# PCI_short_card_universal_-_32_BIT.net
KiCad netlist of a schematic drawn in Altium Designer
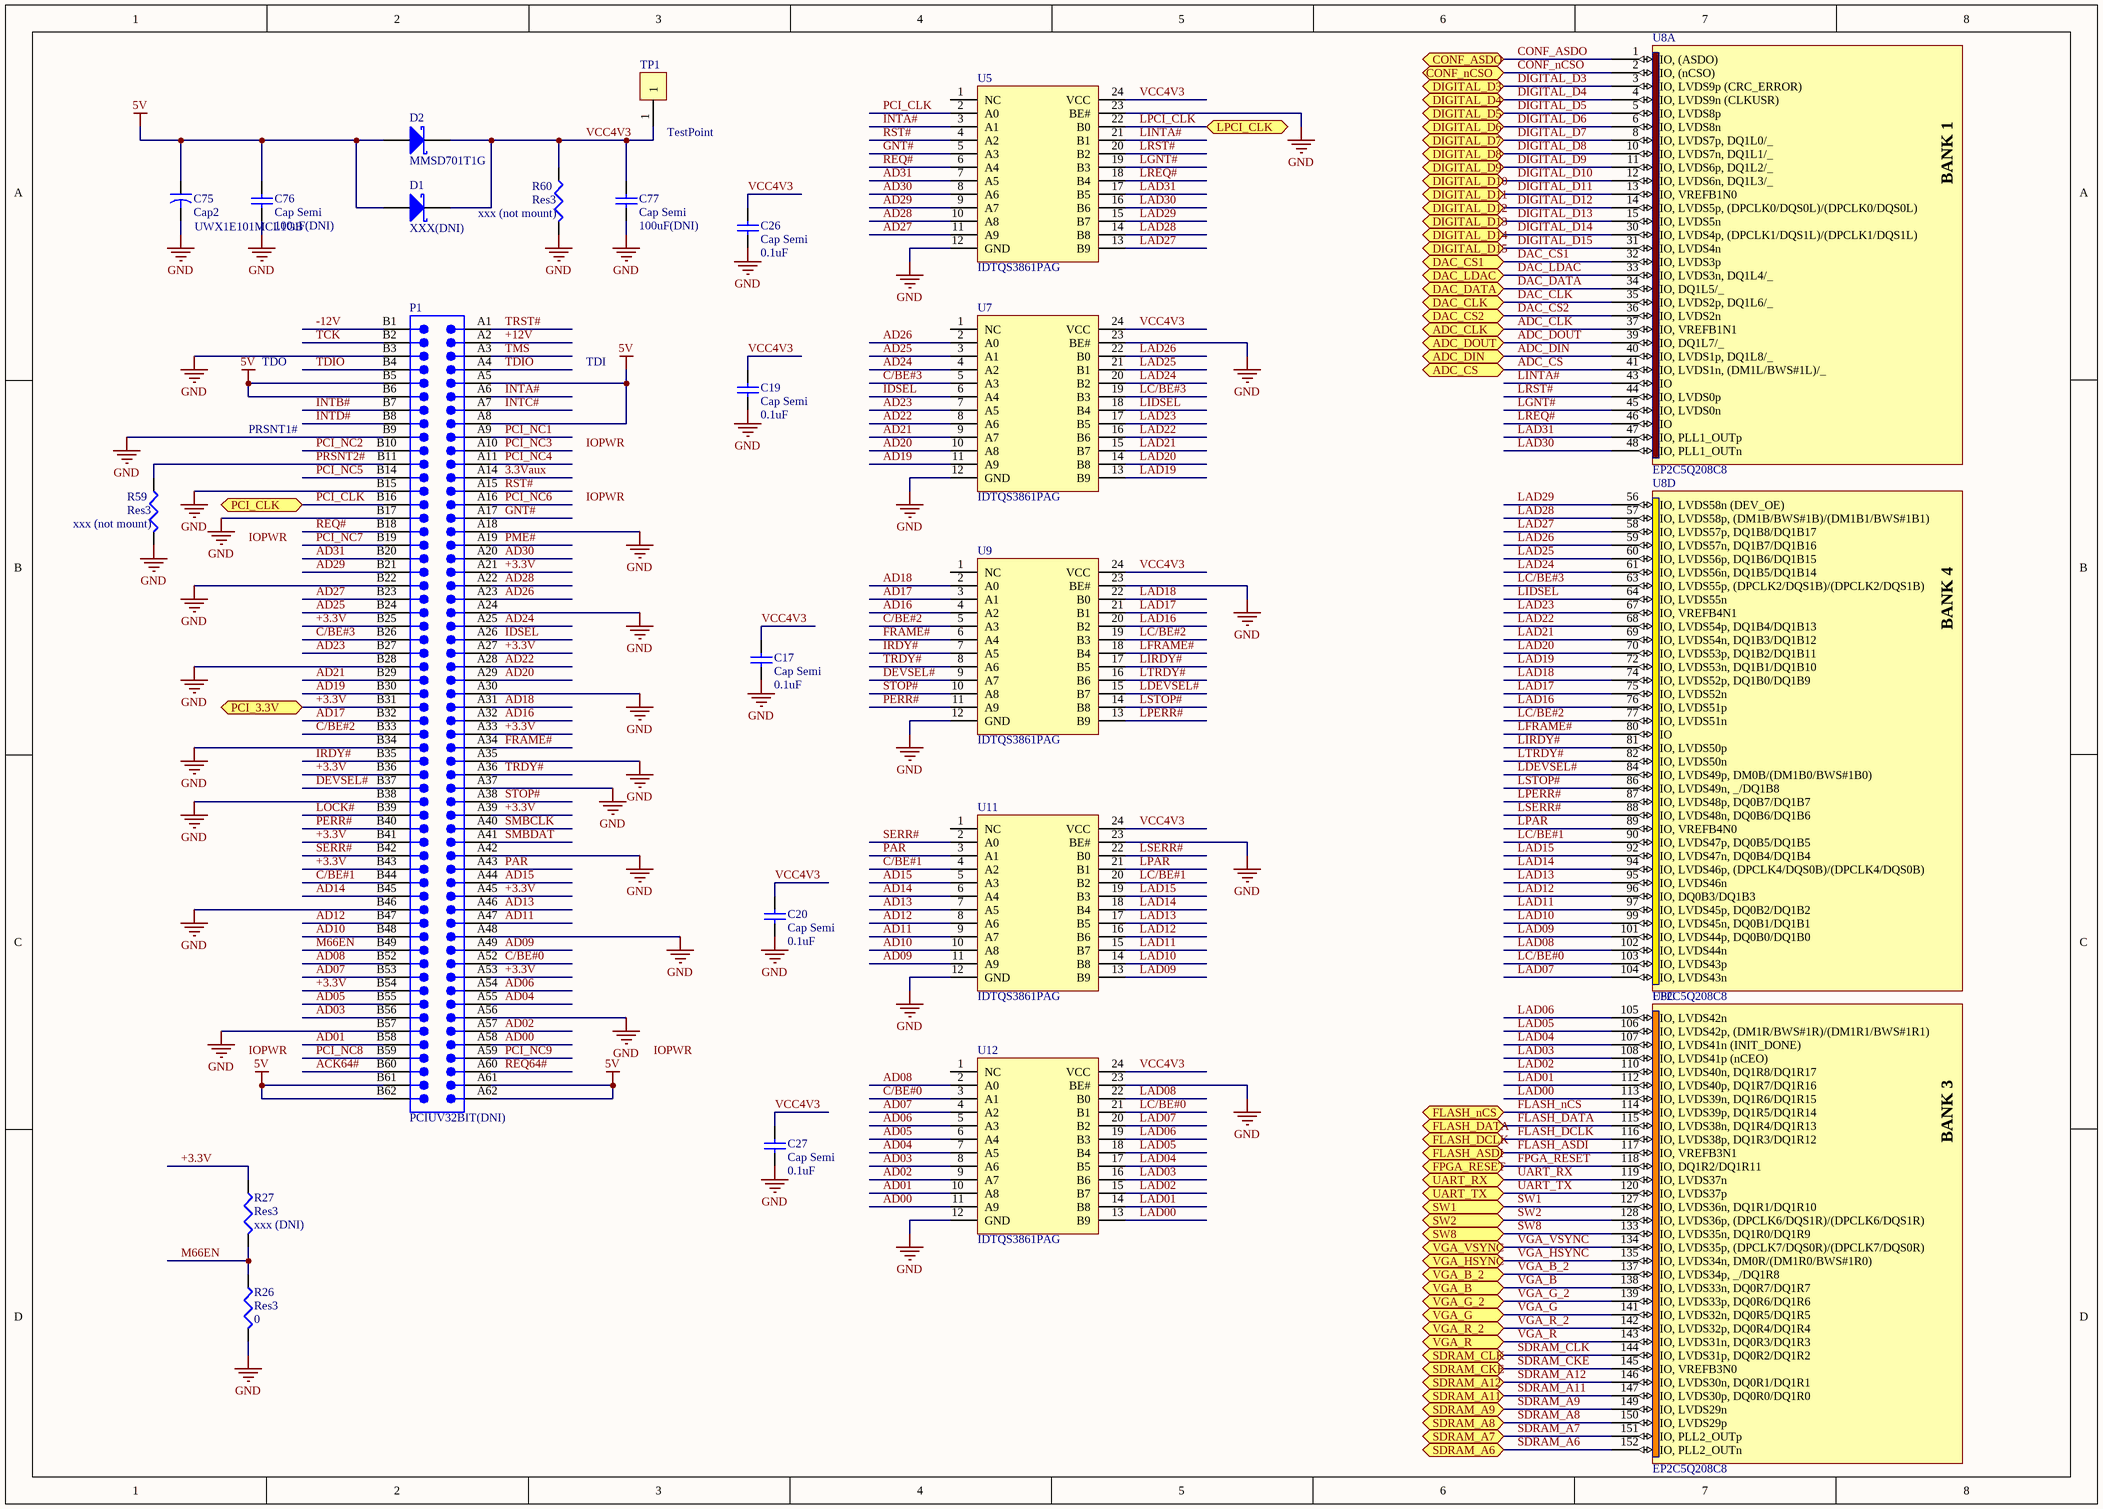
[diagram p0: PCI short card universal - 32 BIT.schdoc]

(export (version "E")
  (design (tool "Eeschema 10.0.6"))
  (components
    (comp (ref "C17")
      (value "Cap Semi")
      (footprint "RESC1608N")
      (description "Capacitor (Semiconductor SIM Model)")
      (fields (field (name "ALTIUM_VALUE") "0.1uF") (field (name "PUBLISHER") "Altium Limited"))
      (libsource (lib "Miscellaneous Devices") (part "Cap Semi"))
    )
    (comp (ref "C19")
      (value "Cap Semi")
      (footprint "RESC1608N")
      (description "Capacitor (Semiconductor SIM Model)")
      (fields (field (name "ALTIUM_VALUE") "0.1uF") (field (name "PUBLISHER") "Altium Limited"))
      (libsource (lib "Miscellaneous Devices") (part "Cap Semi"))
    )
    (comp (ref "C20")
      (value "Cap Semi")
      (footprint "RESC1608N")
      (description "Capacitor (Semiconductor SIM Model)")
      (fields (field (name "ALTIUM_VALUE") "0.1uF") (field (name "PUBLISHER") "Altium Limited"))
      (libsource (lib "Miscellaneous Devices") (part "Cap Semi"))
    )
    (comp (ref "C26")
      (value "Cap Semi")
      (footprint "RESC1608N")
      (description "Capacitor (Semiconductor SIM Model)")
      (fields (field (name "ALTIUM_VALUE") "0.1uF") (field (name "PUBLISHER") "Altium Limited"))
      (libsource (lib "Miscellaneous Devices") (part "Cap Semi"))
    )
    (comp (ref "C27")
      (value "Cap Semi")
      (footprint "RESC1608N")
      (description "Capacitor (Semiconductor SIM Model)")
      (fields (field (name "ALTIUM_VALUE") "0.1uF") (field (name "PUBLISHER") "Altium Limited"))
      (libsource (lib "Miscellaneous Devices") (part "Cap Semi"))
    )
    (comp (ref "C75")
      (value "Cap2")
      (footprint "ECEL_D8")
      (description "NICHICON")
      (fields (field (name "ALTIUM_VALUE") "UWX1E101MCL1GB") (field (name "PUBLISHER") "Altium Limited"))
      (libsource (lib "Miscellaneous Devices") (part "Cap2"))
    )
    (comp (ref "C76")
      (value "Cap Semi")
      (footprint "CD3225-1210")
      (fields (field (name "ALTIUM_VALUE") "100uF(DNI)") (field (name "PUBLISHER") "Altium Limited"))
      (libsource (lib "Miscellaneous Devices") (part "Cap Semi"))
    )
    (comp (ref "C77")
      (value "Cap Semi")
      (footprint "CD3225-1210")
      (fields (field (name "ALTIUM_VALUE") "100uF(DNI)") (field (name "PUBLISHER") "Altium Limited"))
      (libsource (lib "Miscellaneous Devices") (part "Cap Semi"))
    )
    (comp (ref "D1")
      (value "XXX(DNI)")
      (footprint "LED3.2X1.6X1.1")
      (description "Schottky Diode")
      (fields (field (name "PUBLISHER") "Altium Limited"))
      (libsource (lib "Miscellaneous Devices") (part "D Schottky"))
    )
    (comp (ref "D2")
      (value "MMSD701T1G")
      (footprint "SOD-123")
      (description "ON SEMI")
      (fields (field (name "PUBLISHER") "Altium Limited"))
      (libsource (lib "Miscellaneous Devices") (part "D Schottky"))
    )
    (comp (ref "P1")
      (value "PCIUV32BIT(DNI)")
      (footprint "PCIUV32BIT")
      (description "Card, 116-Position")
      (libsource (lib "*") (part "PCIUV32BIT"))
    )
    (comp (ref "R26")
      (value "Res3")
      (footprint "RESC1608N")
      (description "Resistor")
      (fields (field (name "ALTIUM_VALUE") "0") (field (name "PUBLISHER") "Altium Limited"))
      (libsource (lib "Miscellaneous Devices") (part "Res3"))
    )
    (comp (ref "R27")
      (value "Res3")
      (footprint "RESC1608N")
      (description "Resistor")
      (fields (field (name "ALTIUM_VALUE") "xxx (DNI)") (field (name "PUBLISHER") "Altium Limited"))
      (libsource (lib "Miscellaneous Devices") (part "Res3"))
    )
    (comp (ref "R59")
      (value "Res3")
      (footprint "RESC1608N")
      (description "Resistor")
      (fields (field (name "ALTIUM_VALUE") "xxx (not mount)") (field (name "PUBLISHER") "Altium Limited"))
      (libsource (lib "Miscellaneous Devices") (part "Res3"))
    )
    (comp (ref "R60")
      (value "Res3")
      (footprint "RESC1608N")
      (description "Resistor")
      (fields (field (name "ALTIUM_VALUE") "xxx (not mount)") (field (name "PUBLISHER") "Altium Limited"))
      (libsource (lib "Miscellaneous Devices") (part "Res3"))
    )
    (comp (ref "TP1") (value "TestPoint") (footprint "HDR1X1") (libsource (lib "Schlib1") (part "TestPoint")))
    (comp (ref "U5")
      (value "IDTQS3861PAG")
      (footprint "TSSOP24(QS3681)")
      (description "IDT")
      (libsource (lib "Schlib1") (part "QS3861"))
    )
    (comp (ref "U7")
      (value "IDTQS3861PAG")
      (footprint "TSSOP24(QS3681)")
      (description "IDT")
      (libsource (lib "Schlib1") (part "QS3861"))
    )
    (comp (ref "U8")
      (value "EP2C5Q208C8")
      (footprint "PQFP208_N")
      (fields (field (name "PUBLISHER") "Altium Limited"))
      (libsource (lib "Altera Cyclone II") (part "EP2C5Q208C8"))
    )
    (comp (ref "U9")
      (value "IDTQS3861PAG")
      (footprint "TSSOP24(QS3681)")
      (description "IDT")
      (libsource (lib "Schlib1") (part "QS3861"))
    )
    (comp (ref "U11")
      (value "IDTQS3861PAG")
      (footprint "TSSOP24(QS3681)")
      (description "IDT")
      (libsource (lib "Schlib1") (part "QS3861"))
    )
    (comp (ref "U12")
      (value "IDTQS3861PAG")
      (footprint "TSSOP24(QS3681)")
      (description "IDT")
      (libsource (lib "Schlib1") (part "QS3861"))
    )
  )
  (nets
    (net (code "1") (name "/+3.3V") (class "Default")
      (node (ref "P1") (pin "A21") (pinfunction "A21_A21") (pintype "passive"))
      (node (ref "P1") (pin "A27") (pinfunction "A27_A27") (pintype "passive"))
      (node (ref "P1") (pin "A33") (pinfunction "A33_A33") (pintype "passive"))
      (node (ref "P1") (pin "A39") (pinfunction "A39_A39") (pintype "passive"))
      (node (ref "P1") (pin "A45") (pinfunction "A45_A45") (pintype "passive"))
      (node (ref "P1") (pin "A53") (pinfunction "A53_A53") (pintype "passive"))
      (node (ref "P1") (pin "B25") (pinfunction "B25_B25") (pintype "passive"))
      (node (ref "P1") (pin "B31") (pinfunction "B31_B31") (pintype "passive"))
      (node (ref "P1") (pin "B36") (pinfunction "B36_B36") (pintype "passive"))
      (node (ref "P1") (pin "B41") (pinfunction "B41_B41") (pintype "passive"))
      (node (ref "P1") (pin "B43") (pinfunction "B43_B43") (pintype "passive"))
      (node (ref "P1") (pin "B54") (pinfunction "B54_B54") (pintype "passive"))
      (node (ref "R27") (pin "1") (pinfunction "1_1") (pintype "passive"))
    )
    (net (code "2") (name "/+12V") (class "Default")
      (node (ref "P1") (pin "A2") (pinfunction "A2_A2") (pintype "passive"))
    )
    (net (code "3") (name "/-12V") (class "Default")
      (node (ref "P1") (pin "B1") (pinfunction "B1_B1") (pintype "passive"))
    )
    (net (code "4") (name "/3.3Vaux") (class "Default")
      (node (ref "P1") (pin "A14") (pinfunction "A14_A14") (pintype "passive"))
    )
    (net (code "5") (name "/ACK64#") (class "Default")
      (node (ref "P1") (pin "B60") (pinfunction "B60_B60") (pintype "passive"))
    )
    (net (code "6") (name "/AD00") (class "Default")
      (node (ref "P1") (pin "A58") (pinfunction "A58_A58") (pintype "passive"))
      (node (ref "U12") (pin "11") (pinfunction "A9_11") (pintype "passive"))
    )
    (net (code "7") (name "/AD01") (class "Default")
      (node (ref "P1") (pin "B58") (pinfunction "B58_B58") (pintype "passive"))
      (node (ref "U12") (pin "10") (pinfunction "A8_10") (pintype "passive"))
    )
    (net (code "8") (name "/AD02") (class "Default")
      (node (ref "P1") (pin "A57") (pinfunction "A57_A57") (pintype "passive"))
      (node (ref "U12") (pin "9") (pinfunction "A7_9") (pintype "passive"))
    )
    (net (code "9") (name "/AD03") (class "Default")
      (node (ref "P1") (pin "B56") (pinfunction "B56_B56") (pintype "passive"))
      (node (ref "U12") (pin "8") (pinfunction "A6_8") (pintype "passive"))
    )
    (net (code "10") (name "/AD04") (class "Default")
      (node (ref "P1") (pin "A55") (pinfunction "A55_A55") (pintype "passive"))
      (node (ref "U12") (pin "7") (pinfunction "A5_7") (pintype "passive"))
    )
    (net (code "11") (name "/AD05") (class "Default")
      (node (ref "P1") (pin "B55") (pinfunction "B55_B55") (pintype "passive"))
      (node (ref "U12") (pin "6") (pinfunction "A4_6") (pintype "passive"))
    )
    (net (code "12") (name "/AD06") (class "Default")
      (node (ref "P1") (pin "A54") (pinfunction "A54_A54") (pintype "passive"))
      (node (ref "U12") (pin "5") (pinfunction "A3_5") (pintype "passive"))
    )
    (net (code "13") (name "/AD07") (class "Default")
      (node (ref "P1") (pin "B53") (pinfunction "B53_B53") (pintype "passive"))
      (node (ref "U12") (pin "4") (pinfunction "A2_4") (pintype "passive"))
    )
    (net (code "14") (name "/AD08") (class "Default")
      (node (ref "P1") (pin "B52") (pinfunction "B52_B52") (pintype "passive"))
      (node (ref "U12") (pin "2") (pinfunction "A0_2") (pintype "passive"))
    )
    (net (code "15") (name "/AD09") (class "Default")
      (node (ref "P1") (pin "A49") (pinfunction "A49_A49") (pintype "passive"))
      (node (ref "U11") (pin "11") (pinfunction "A9_11") (pintype "passive"))
    )
    (net (code "16") (name "/AD10") (class "Default")
      (node (ref "P1") (pin "B48") (pinfunction "B48_B48") (pintype "passive"))
      (node (ref "U11") (pin "10") (pinfunction "A8_10") (pintype "passive"))
    )
    (net (code "17") (name "/AD11") (class "Default")
      (node (ref "P1") (pin "A47") (pinfunction "A47_A47") (pintype "passive"))
      (node (ref "U11") (pin "9") (pinfunction "A7_9") (pintype "passive"))
    )
    (net (code "18") (name "/AD12") (class "Default")
      (node (ref "P1") (pin "B47") (pinfunction "B47_B47") (pintype "passive"))
      (node (ref "U11") (pin "8") (pinfunction "A6_8") (pintype "passive"))
    )
    (net (code "19") (name "/AD13") (class "Default")
      (node (ref "P1") (pin "A46") (pinfunction "A46_A46") (pintype "passive"))
      (node (ref "U11") (pin "7") (pinfunction "A5_7") (pintype "passive"))
    )
    (net (code "20") (name "/AD14") (class "Default")
      (node (ref "P1") (pin "B45") (pinfunction "B45_B45") (pintype "passive"))
      (node (ref "U11") (pin "6") (pinfunction "A4_6") (pintype "passive"))
    )
    (net (code "21") (name "/AD15") (class "Default")
      (node (ref "P1") (pin "A44") (pinfunction "A44_A44") (pintype "passive"))
      (node (ref "U11") (pin "5") (pinfunction "A3_5") (pintype "passive"))
    )
    (net (code "22") (name "/AD16") (class "Default")
      (node (ref "P1") (pin "A32") (pinfunction "A32_A32") (pintype "passive"))
      (node (ref "U9") (pin "4") (pinfunction "A2_4") (pintype "passive"))
    )
    (net (code "23") (name "/AD17") (class "Default")
      (node (ref "P1") (pin "B32") (pinfunction "B32_B32") (pintype "passive"))
      (node (ref "U9") (pin "3") (pinfunction "A1_3") (pintype "passive"))
    )
    (net (code "24") (name "/AD18") (class "Default")
      (node (ref "P1") (pin "A31") (pinfunction "A31_A31") (pintype "passive"))
      (node (ref "U9") (pin "2") (pinfunction "A0_2") (pintype "passive"))
    )
    (net (code "25") (name "/AD19") (class "Default")
      (node (ref "P1") (pin "B30") (pinfunction "B30_B30") (pintype "passive"))
      (node (ref "U7") (pin "11") (pinfunction "A9_11") (pintype "passive"))
    )
    (net (code "26") (name "/AD20") (class "Default")
      (node (ref "P1") (pin "A29") (pinfunction "A29_A29") (pintype "passive"))
      (node (ref "U7") (pin "10") (pinfunction "A8_10") (pintype "passive"))
    )
    (net (code "27") (name "/AD21") (class "Default")
      (node (ref "P1") (pin "B29") (pinfunction "B29_B29") (pintype "passive"))
      (node (ref "U7") (pin "9") (pinfunction "A7_9") (pintype "passive"))
    )
    (net (code "28") (name "/AD22") (class "Default")
      (node (ref "P1") (pin "A28") (pinfunction "A28_A28") (pintype "passive"))
      (node (ref "U7") (pin "8") (pinfunction "A6_8") (pintype "passive"))
    )
    (net (code "29") (name "/AD23") (class "Default")
      (node (ref "P1") (pin "B27") (pinfunction "B27_B27") (pintype "passive"))
      (node (ref "U7") (pin "7") (pinfunction "A5_7") (pintype "passive"))
    )
    (net (code "30") (name "/AD24") (class "Default")
      (node (ref "P1") (pin "A25") (pinfunction "A25_A25") (pintype "passive"))
      (node (ref "U7") (pin "4") (pinfunction "A2_4") (pintype "passive"))
    )
    (net (code "31") (name "/AD25") (class "Default")
      (node (ref "P1") (pin "B24") (pinfunction "B24_B24") (pintype "passive"))
      (node (ref "U7") (pin "3") (pinfunction "A1_3") (pintype "passive"))
    )
    (net (code "32") (name "/AD26") (class "Default")
      (node (ref "P1") (pin "A23") (pinfunction "A23_A23") (pintype "passive"))
      (node (ref "U7") (pin "2") (pinfunction "A0_2") (pintype "passive"))
    )
    (net (code "33") (name "/AD27") (class "Default")
      (node (ref "P1") (pin "B23") (pinfunction "B23_B23") (pintype "passive"))
      (node (ref "U5") (pin "11") (pinfunction "A9_11") (pintype "passive"))
    )
    (net (code "34") (name "/AD28") (class "Default")
      (node (ref "P1") (pin "A22") (pinfunction "A22_A22") (pintype "passive"))
      (node (ref "U5") (pin "10") (pinfunction "A8_10") (pintype "passive"))
    )
    (net (code "35") (name "/AD29") (class "Default")
      (node (ref "P1") (pin "B21") (pinfunction "B21_B21") (pintype "passive"))
      (node (ref "U5") (pin "9") (pinfunction "A7_9") (pintype "passive"))
    )
    (net (code "36") (name "/AD30") (class "Default")
      (node (ref "P1") (pin "A20") (pinfunction "A20_A20") (pintype "passive"))
      (node (ref "U5") (pin "8") (pinfunction "A6_8") (pintype "passive"))
    )
    (net (code "37") (name "/AD31") (class "Default")
      (node (ref "P1") (pin "B20") (pinfunction "B20_B20") (pintype "passive"))
      (node (ref "U5") (pin "7") (pinfunction "A5_7") (pintype "passive"))
    )
    (net (code "38") (name "/ADC_CLK") (class "Default")
      (node (ref "U8") (pin "37") (pinfunction "IO,_VREFB1N1_37") (pintype "bidirectional"))
    )
    (net (code "39") (name "/ADC_CS") (class "Default")
      (node (ref "U8") (pin "41") (pinfunction "IO,_LVDS1n,_(DM1L/BWS#1L)/__41") (pintype "bidirectional"))
    )
    (net (code "40") (name "/ADC_DIN") (class "Default")
      (node (ref "U8") (pin "40") (pinfunction "IO,_LVDS1p,_DQ1L8/__40") (pintype "bidirectional"))
    )
    (net (code "41") (name "/ADC_DOUT") (class "Default")
      (node (ref "U8") (pin "39") (pinfunction "IO,_DQ1L7/__39") (pintype "bidirectional"))
    )
    (net (code "42") (name "/CONF_ASDO") (class "Default")
      (node (ref "U8") (pin "1") (pinfunction "IO,_(ASDO)_1") (pintype "bidirectional"))
    )
    (net (code "43") (name "/CONF_nCSO") (class "Default")
      (node (ref "U8") (pin "2") (pinfunction "IO,_(nCSO)_2") (pintype "bidirectional"))
    )
    (net (code "44") (name "/C{slash}BE#0") (class "Default")
      (node (ref "P1") (pin "A52") (pinfunction "A52_A52") (pintype "passive"))
      (node (ref "U12") (pin "3") (pinfunction "A1_3") (pintype "passive"))
    )
    (net (code "45") (name "/C{slash}BE#1") (class "Default")
      (node (ref "P1") (pin "B44") (pinfunction "B44_B44") (pintype "passive"))
      (node (ref "U11") (pin "4") (pinfunction "A2_4") (pintype "passive"))
    )
    (net (code "46") (name "/C{slash}BE#2") (class "Default")
      (node (ref "P1") (pin "B33") (pinfunction "B33_B33") (pintype "passive"))
      (node (ref "U9") (pin "5") (pinfunction "A3_5") (pintype "passive"))
    )
    (net (code "47") (name "/C{slash}BE#3") (class "Default")
      (node (ref "P1") (pin "B26") (pinfunction "B26_B26") (pintype "passive"))
      (node (ref "U7") (pin "5") (pinfunction "A3_5") (pintype "passive"))
    )
    (net (code "48") (name "/DAC_CLK") (class "Default")
      (node (ref "U8") (pin "35") (pinfunction "IO,_LVDS2p,_DQ1L6/__35") (pintype "bidirectional"))
    )
    (net (code "49") (name "/DAC_CS1") (class "Default")
      (node (ref "U8") (pin "32") (pinfunction "IO,_LVDS3p_32") (pintype "bidirectional"))
    )
    (net (code "50") (name "/DAC_CS2") (class "Default")
      (node (ref "U8") (pin "36") (pinfunction "IO,_LVDS2n_36") (pintype "bidirectional"))
    )
    (net (code "51") (name "/DAC_DATA") (class "Default")
      (node (ref "U8") (pin "34") (pinfunction "IO,_DQ1L5/__34") (pintype "bidirectional"))
    )
    (net (code "52") (name "/DAC_LDAC") (class "Default")
      (node (ref "U8") (pin "33") (pinfunction "IO,_LVDS3n,_DQ1L4/__33") (pintype "bidirectional"))
    )
    (net (code "53") (name "/DEVSEL#") (class "Default")
      (node (ref "P1") (pin "B37") (pinfunction "B37_B37") (pintype "passive"))
      (node (ref "U9") (pin "9") (pinfunction "A7_9") (pintype "passive"))
    )
    (net (code "54") (name "/DIGITAL_D3") (class "Default")
      (node (ref "U8") (pin "3") (pinfunction "IO,_LVDS9p_(CRC_ERROR)_3") (pintype "bidirectional"))
    )
    (net (code "55") (name "/DIGITAL_D4") (class "Default")
      (node (ref "U8") (pin "4") (pinfunction "IO,_LVDS9n_(CLKUSR)_4") (pintype "bidirectional"))
    )
    (net (code "56") (name "/DIGITAL_D5") (class "Default")
      (node (ref "U8") (pin "5") (pinfunction "IO,_LVDS8p_5") (pintype "bidirectional"))
    )
    (net (code "57") (name "/DIGITAL_D6") (class "Default")
      (node (ref "U8") (pin "6") (pinfunction "IO,_LVDS8n_6") (pintype "bidirectional"))
    )
    (net (code "58") (name "/DIGITAL_D7") (class "Default")
      (node (ref "U8") (pin "8") (pinfunction "IO,_LVDS7p,_DQ1L0/__8") (pintype "bidirectional"))
    )
    (net (code "59") (name "/DIGITAL_D8") (class "Default")
      (node (ref "U8") (pin "10") (pinfunction "IO,_LVDS7n,_DQ1L1/__10") (pintype "bidirectional"))
    )
    (net (code "60") (name "/DIGITAL_D9") (class "Default")
      (node (ref "U8") (pin "11") (pinfunction "IO,_LVDS6p,_DQ1L2/__11") (pintype "bidirectional"))
    )
    (net (code "61") (name "/DIGITAL_D10") (class "Default")
      (node (ref "U8") (pin "12") (pinfunction "IO,_LVDS6n,_DQ1L3/__12") (pintype "bidirectional"))
    )
    (net (code "62") (name "/DIGITAL_D11") (class "Default")
      (node (ref "U8") (pin "13") (pinfunction "IO,_VREFB1N0_13") (pintype "bidirectional"))
    )
    (net (code "63") (name "/DIGITAL_D12") (class "Default")
      (node (ref "U8") (pin "14") (pinfunction "IO,_LVDS5p,_(DPCLK0/DQS0L)/(DPCLK0/DQS0L)_14") (pintype "bidirectional"))
    )
    (net (code "64") (name "/DIGITAL_D13") (class "Default")
      (node (ref "U8") (pin "15") (pinfunction "IO,_LVDS5n_15") (pintype "bidirectional"))
    )
    (net (code "65") (name "/DIGITAL_D14") (class "Default")
      (node (ref "U8") (pin "30") (pinfunction "IO,_LVDS4p,_(DPCLK1/DQS1L)/(DPCLK1/DQS1L)_30") (pintype "bidirectional"))
    )
    (net (code "66") (name "/DIGITAL_D15") (class "Default")
      (node (ref "U8") (pin "31") (pinfunction "IO,_LVDS4n_31") (pintype "bidirectional"))
    )
    (net (code "67") (name "/FLASH_ASDI") (class "Default")
      (node (ref "U8") (pin "117") (pinfunction "IO,_VREFB3N1_117") (pintype "bidirectional"))
    )
    (net (code "68") (name "/FLASH_DATA") (class "Default")
      (node (ref "U8") (pin "115") (pinfunction "IO,_LVDS38n,_DQ1R4/DQ1R13_115") (pintype "bidirectional"))
    )
    (net (code "69") (name "/FLASH_DCLK") (class "Default")
      (node (ref "U8") (pin "116") (pinfunction "IO,_LVDS38p,_DQ1R3/DQ1R12_116") (pintype "bidirectional"))
    )
    (net (code "70") (name "/FLASH_nCS") (class "Default")
      (node (ref "U8") (pin "114") (pinfunction "IO,_LVDS39p,_DQ1R5/DQ1R14_114") (pintype "bidirectional"))
    )
    (net (code "71") (name "/FPGA_RESET") (class "Default")
      (node (ref "U8") (pin "118") (pinfunction "IO,_DQ1R2/DQ1R11_118") (pintype "bidirectional"))
    )
    (net (code "72") (name "/FRAME#") (class "Default")
      (node (ref "P1") (pin "A34") (pinfunction "A34_A34") (pintype "passive"))
      (node (ref "U9") (pin "6") (pinfunction "A4_6") (pintype "passive"))
    )
    (net (code "73") (name "/GNT#") (class "Default")
      (node (ref "P1") (pin "A17") (pinfunction "A17_A17") (pintype "passive"))
      (node (ref "U5") (pin "5") (pinfunction "A3_5") (pintype "passive"))
    )
    (net (code "74") (name "/IDSEL") (class "Default")
      (node (ref "P1") (pin "A26") (pinfunction "A26_A26") (pintype "passive"))
      (node (ref "U7") (pin "6") (pinfunction "A4_6") (pintype "passive"))
    )
    (net (code "75") (name "/INTA#") (class "Default")
      (node (ref "P1") (pin "A6") (pinfunction "A6_A6") (pintype "passive"))
      (node (ref "U5") (pin "3") (pinfunction "A1_3") (pintype "passive"))
    )
    (net (code "76") (name "/INTB#") (class "Default")
      (node (ref "P1") (pin "B7") (pinfunction "B7_B7") (pintype "passive"))
    )
    (net (code "77") (name "/INTC#") (class "Default")
      (node (ref "P1") (pin "A7") (pinfunction "A7_A7") (pintype "passive"))
    )
    (net (code "78") (name "/INTD#") (class "Default")
      (node (ref "P1") (pin "B8") (pinfunction "B8_B8") (pintype "passive"))
    )
    (net (code "80") (name "/IRDY#") (class "Default")
      (node (ref "P1") (pin "B35") (pinfunction "B35_B35") (pintype "passive"))
      (node (ref "U9") (pin "7") (pinfunction "A5_7") (pintype "passive"))
    )
    (net (code "81") (name "/LAD00") (class "Default")
      (node (ref "U12") (pin "13") (pinfunction "B9_13") (pintype "passive"))
      (node (ref "U8") (pin "113") (pinfunction "IO,_LVDS39n,_DQ1R6/DQ1R15_113") (pintype "bidirectional"))
    )
    (net (code "82") (name "/LAD01") (class "Default")
      (node (ref "U12") (pin "14") (pinfunction "B8_14") (pintype "passive"))
      (node (ref "U8") (pin "112") (pinfunction "IO,_LVDS40p,_DQ1R7/DQ1R16_112") (pintype "bidirectional"))
    )
    (net (code "83") (name "/LAD02") (class "Default")
      (node (ref "U12") (pin "15") (pinfunction "B7_15") (pintype "passive"))
      (node (ref "U8") (pin "110") (pinfunction "IO,_LVDS40n,_DQ1R8/DQ1R17_110") (pintype "bidirectional"))
    )
    (net (code "84") (name "/LAD03") (class "Default")
      (node (ref "U12") (pin "16") (pinfunction "B6_16") (pintype "passive"))
      (node (ref "U8") (pin "108") (pinfunction "IO,_LVDS41p_(nCEO)_108") (pintype "bidirectional"))
    )
    (net (code "85") (name "/LAD04") (class "Default")
      (node (ref "U12") (pin "17") (pinfunction "B5_17") (pintype "passive"))
      (node (ref "U8") (pin "107") (pinfunction "IO,_LVDS41n_(INIT_DONE)_107") (pintype "bidirectional"))
    )
    (net (code "86") (name "/LAD05") (class "Default")
      (node (ref "U12") (pin "18") (pinfunction "B4_18") (pintype "passive"))
      (node (ref "U8") (pin "106") (pinfunction "IO,_LVDS42p,_(DM1R/BWS#1R)/(DM1R1/BWS#1R1)_106") (pintype "bidirectional"))
    )
    (net (code "87") (name "/LAD06") (class "Default")
      (node (ref "U12") (pin "19") (pinfunction "B3_19") (pintype "passive"))
      (node (ref "U8") (pin "105") (pinfunction "IO,_LVDS42n_105") (pintype "bidirectional"))
    )
    (net (code "88") (name "/LAD07") (class "Default")
      (node (ref "U12") (pin "20") (pinfunction "B2_20") (pintype "passive"))
      (node (ref "U8") (pin "104") (pinfunction "IO,_LVDS43n_104") (pintype "bidirectional"))
    )
    (net (code "89") (name "/LAD08") (class "Default")
      (node (ref "U12") (pin "22") (pinfunction "B0_22") (pintype "passive"))
      (node (ref "U8") (pin "102") (pinfunction "IO,_LVDS44n_102") (pintype "bidirectional"))
    )
    (net (code "90") (name "/LAD09") (class "Default")
      (node (ref "U11") (pin "13") (pinfunction "B9_13") (pintype "passive"))
      (node (ref "U8") (pin "101") (pinfunction "IO,_LVDS44p,_DQ0B0/DQ1B0_101") (pintype "bidirectional"))
    )
    (net (code "91") (name "/LAD10") (class "Default")
      (node (ref "U11") (pin "14") (pinfunction "B8_14") (pintype "passive"))
      (node (ref "U8") (pin "99") (pinfunction "IO,_LVDS45n,_DQ0B1/DQ1B1_99") (pintype "bidirectional"))
    )
    (net (code "92") (name "/LAD11") (class "Default")
      (node (ref "U11") (pin "15") (pinfunction "B7_15") (pintype "passive"))
      (node (ref "U8") (pin "97") (pinfunction "IO,_LVDS45p,_DQ0B2/DQ1B2_97") (pintype "bidirectional"))
    )
    (net (code "93") (name "/LAD12") (class "Default")
      (node (ref "U11") (pin "16") (pinfunction "B6_16") (pintype "passive"))
      (node (ref "U8") (pin "96") (pinfunction "IO,_DQ0B3/DQ1B3_96") (pintype "bidirectional"))
    )
    (net (code "94") (name "/LAD13") (class "Default")
      (node (ref "U11") (pin "17") (pinfunction "B5_17") (pintype "passive"))
      (node (ref "U8") (pin "95") (pinfunction "IO,_LVDS46n_95") (pintype "bidirectional"))
    )
    (net (code "95") (name "/LAD14") (class "Default")
      (node (ref "U11") (pin "18") (pinfunction "B4_18") (pintype "passive"))
      (node (ref "U8") (pin "94") (pinfunction "IO,_LVDS46p,_(DPCLK4/DQS0B)/(DPCLK4/DQS0B)_94") (pintype "bidirectional"))
    )
    (net (code "96") (name "/LAD15") (class "Default")
      (node (ref "U11") (pin "19") (pinfunction "B3_19") (pintype "passive"))
      (node (ref "U8") (pin "92") (pinfunction "IO,_LVDS47n,_DQ0B4/DQ1B4_92") (pintype "bidirectional"))
    )
    (net (code "97") (name "/LAD16") (class "Default")
      (node (ref "U8") (pin "76") (pinfunction "IO,_LVDS51p_76") (pintype "bidirectional"))
      (node (ref "U9") (pin "20") (pinfunction "B2_20") (pintype "passive"))
    )
    (net (code "98") (name "/LAD17") (class "Default")
      (node (ref "U8") (pin "75") (pinfunction "IO,_LVDS52n_75") (pintype "bidirectional"))
      (node (ref "U9") (pin "21") (pinfunction "B1_21") (pintype "passive"))
    )
    (net (code "99") (name "/LAD18") (class "Default")
      (node (ref "U8") (pin "74") (pinfunction "IO,_LVDS52p,_DQ1B0/DQ1B9_74") (pintype "bidirectional"))
      (node (ref "U9") (pin "22") (pinfunction "B0_22") (pintype "passive"))
    )
    (net (code "100") (name "/LAD19") (class "Default")
      (node (ref "U7") (pin "13") (pinfunction "B9_13") (pintype "passive"))
      (node (ref "U8") (pin "72") (pinfunction "IO,_LVDS53n,_DQ1B1/DQ1B10_72") (pintype "bidirectional"))
    )
    (net (code "101") (name "/LAD20") (class "Default")
      (node (ref "U7") (pin "14") (pinfunction "B8_14") (pintype "passive"))
      (node (ref "U8") (pin "70") (pinfunction "IO,_LVDS53p,_DQ1B2/DQ1B11_70") (pintype "bidirectional"))
    )
    (net (code "102") (name "/LAD21") (class "Default")
      (node (ref "U7") (pin "15") (pinfunction "B7_15") (pintype "passive"))
      (node (ref "U8") (pin "69") (pinfunction "IO,_LVDS54n,_DQ1B3/DQ1B12_69") (pintype "bidirectional"))
    )
    (net (code "103") (name "/LAD22") (class "Default")
      (node (ref "U7") (pin "16") (pinfunction "B6_16") (pintype "passive"))
      (node (ref "U8") (pin "68") (pinfunction "IO,_LVDS54p,_DQ1B4/DQ1B13_68") (pintype "bidirectional"))
    )
    (net (code "104") (name "/LAD23") (class "Default")
      (node (ref "U7") (pin "17") (pinfunction "B5_17") (pintype "passive"))
      (node (ref "U8") (pin "67") (pinfunction "IO,_VREFB4N1_67") (pintype "bidirectional"))
    )
    (net (code "105") (name "/LAD24") (class "Default")
      (node (ref "U7") (pin "20") (pinfunction "B2_20") (pintype "passive"))
      (node (ref "U8") (pin "61") (pinfunction "IO,_LVDS56n,_DQ1B5/DQ1B14_61") (pintype "bidirectional"))
    )
    (net (code "106") (name "/LAD25") (class "Default")
      (node (ref "U7") (pin "21") (pinfunction "B1_21") (pintype "passive"))
      (node (ref "U8") (pin "60") (pinfunction "IO,_LVDS56p,_DQ1B6/DQ1B15_60") (pintype "bidirectional"))
    )
    (net (code "107") (name "/LAD26") (class "Default")
      (node (ref "U7") (pin "22") (pinfunction "B0_22") (pintype "passive"))
      (node (ref "U8") (pin "59") (pinfunction "IO,_LVDS57n,_DQ1B7/DQ1B16_59") (pintype "bidirectional"))
    )
    (net (code "108") (name "/LAD27") (class "Default")
      (node (ref "U5") (pin "13") (pinfunction "B9_13") (pintype "passive"))
      (node (ref "U8") (pin "58") (pinfunction "IO,_LVDS57p,_DQ1B8/DQ1B17_58") (pintype "bidirectional"))
    )
    (net (code "109") (name "/LAD28") (class "Default")
      (node (ref "U5") (pin "14") (pinfunction "B8_14") (pintype "passive"))
      (node (ref "U8") (pin "57") (pinfunction "IO,_LVDS58p,_(DM1B/BWS#1B)/(DM1B1/BWS#1B1)_57") (pintype "bidirectional"))
    )
    (net (code "110") (name "/LAD29") (class "Default")
      (node (ref "U5") (pin "15") (pinfunction "B7_15") (pintype "passive"))
      (node (ref "U8") (pin "56") (pinfunction "IO,_LVDS58n_(DEV_OE)_56") (pintype "bidirectional"))
    )
    (net (code "111") (name "/LAD30") (class "Default")
      (node (ref "U5") (pin "16") (pinfunction "B6_16") (pintype "passive"))
      (node (ref "U8") (pin "48") (pinfunction "IO,_PLL1_OUTn_48") (pintype "bidirectional"))
    )
    (net (code "112") (name "/LAD31") (class "Default")
      (node (ref "U5") (pin "17") (pinfunction "B5_17") (pintype "passive"))
      (node (ref "U8") (pin "47") (pinfunction "IO,_PLL1_OUTp_47") (pintype "bidirectional"))
    )
    (net (code "113") (name "/LC{slash}BE#0") (class "Default")
      (node (ref "U12") (pin "21") (pinfunction "B1_21") (pintype "passive"))
      (node (ref "U8") (pin "103") (pinfunction "IO,_LVDS43p_103") (pintype "bidirectional"))
    )
    (net (code "114") (name "/LC{slash}BE#1") (class "Default")
      (node (ref "U11") (pin "20") (pinfunction "B2_20") (pintype "passive"))
      (node (ref "U8") (pin "90") (pinfunction "IO,_LVDS47p,_DQ0B5/DQ1B5_90") (pintype "bidirectional"))
    )
    (net (code "115") (name "/LC{slash}BE#2") (class "Default")
      (node (ref "U8") (pin "77") (pinfunction "IO,_LVDS51n_77") (pintype "bidirectional"))
      (node (ref "U9") (pin "19") (pinfunction "B3_19") (pintype "passive"))
    )
    (net (code "116") (name "/LC{slash}BE#3") (class "Default")
      (node (ref "U7") (pin "19") (pinfunction "B3_19") (pintype "passive"))
      (node (ref "U8") (pin "63") (pinfunction "IO,_LVDS55p,_(DPCLK2/DQS1B)/(DPCLK2/DQS1B)_63") (pintype "bidirectional"))
    )
    (net (code "117") (name "/LDEVSEL#") (class "Default")
      (node (ref "U8") (pin "84") (pinfunction "IO,_LVDS49p,_DM0B/(DM1B0/BWS#1B0)_84") (pintype "bidirectional"))
      (node (ref "U9") (pin "15") (pinfunction "B7_15") (pintype "passive"))
    )
    (net (code "118") (name "/LFRAME#") (class "Default")
      (node (ref "U8") (pin "80") (pinfunction "IO_80") (pintype "bidirectional"))
      (node (ref "U9") (pin "18") (pinfunction "B4_18") (pintype "passive"))
    )
    (net (code "119") (name "/LGNT#") (class "Default")
      (node (ref "U5") (pin "19") (pinfunction "B3_19") (pintype "passive"))
      (node (ref "U8") (pin "45") (pinfunction "IO,_LVDS0n_45") (pintype "bidirectional"))
    )
    (net (code "120") (name "/LIDSEL") (class "Default")
      (node (ref "U7") (pin "18") (pinfunction "B4_18") (pintype "passive"))
      (node (ref "U8") (pin "64") (pinfunction "IO,_LVDS55n_64") (pintype "bidirectional"))
    )
    (net (code "121") (name "/LINTA#") (class "Default")
      (node (ref "U5") (pin "21") (pinfunction "B1_21") (pintype "passive"))
      (node (ref "U8") (pin "43") (pinfunction "IO_43") (pintype "bidirectional"))
    )
    (net (code "122") (name "/LIRDY#") (class "Default")
      (node (ref "U8") (pin "81") (pinfunction "IO,_LVDS50p_81") (pintype "bidirectional"))
      (node (ref "U9") (pin "17") (pinfunction "B5_17") (pintype "passive"))
    )
    (net (code "123") (name "/LOCK#") (class "Default")
      (node (ref "P1") (pin "B39") (pinfunction "B39_B39") (pintype "passive"))
    )
    (net (code "124") (name "/LPAR") (class "Default")
      (node (ref "U11") (pin "21") (pinfunction "B1_21") (pintype "passive"))
      (node (ref "U8") (pin "89") (pinfunction "IO,_VREFB4N0_89") (pintype "bidirectional"))
    )
    (net (code "125") (name "/LPCI_CLK") (class "Default")
      (node (ref "U5") (pin "22") (pinfunction "B0_22") (pintype "passive"))
    )
    (net (code "126") (name "/LPERR#") (class "Default")
      (node (ref "U8") (pin "87") (pinfunction "IO,_LVDS48p,_DQ0B7/DQ1B7_87") (pintype "bidirectional"))
      (node (ref "U9") (pin "13") (pinfunction "B9_13") (pintype "passive"))
    )
    (net (code "127") (name "/LREQ#") (class "Default")
      (node (ref "U5") (pin "18") (pinfunction "B4_18") (pintype "passive"))
      (node (ref "U8") (pin "46") (pinfunction "IO_46") (pintype "bidirectional"))
    )
    (net (code "128") (name "/LRST#") (class "Default")
      (node (ref "U5") (pin "20") (pinfunction "B2_20") (pintype "passive"))
      (node (ref "U8") (pin "44") (pinfunction "IO,_LVDS0p_44") (pintype "bidirectional"))
    )
    (net (code "129") (name "/LSERR#") (class "Default")
      (node (ref "U11") (pin "22") (pinfunction "B0_22") (pintype "passive"))
      (node (ref "U8") (pin "88") (pinfunction "IO,_LVDS48n,_DQ0B6/DQ1B6_88") (pintype "bidirectional"))
    )
    (net (code "130") (name "/LSTOP#") (class "Default")
      (node (ref "U8") (pin "86") (pinfunction "IO,_LVDS49n,__/DQ1B8_86") (pintype "bidirectional"))
      (node (ref "U9") (pin "14") (pinfunction "B8_14") (pintype "passive"))
    )
    (net (code "131") (name "/LTRDY#") (class "Default")
      (node (ref "U8") (pin "82") (pinfunction "IO,_LVDS50n_82") (pintype "bidirectional"))
      (node (ref "U9") (pin "16") (pinfunction "B6_16") (pintype "passive"))
    )
    (net (code "132") (name "/M66EN") (class "Default")
      (node (ref "P1") (pin "B49") (pinfunction "B49_B49") (pintype "passive"))
      (node (ref "R26") (pin "1") (pinfunction "1_1") (pintype "passive"))
      (node (ref "R27") (pin "2") (pinfunction "2_2") (pintype "passive"))
    )
    (net (code "133") (name "/PAR") (class "Default")
      (node (ref "P1") (pin "A43") (pinfunction "A43_A43") (pintype "passive"))
      (node (ref "U11") (pin "3") (pinfunction "A1_3") (pintype "passive"))
    )
    (net (code "134") (name "/PCI_CLK") (class "Default")
      (node (ref "P1") (pin "B16") (pinfunction "B16_B16") (pintype "passive"))
      (node (ref "U5") (pin "2") (pinfunction "A0_2") (pintype "passive"))
    )
    (net (code "135") (name "/PCI_NC1") (class "Default")
      (node (ref "P1") (pin "A9") (pinfunction "A9_A9") (pintype "passive"))
    )
    (net (code "136") (name "/PCI_NC2") (class "Default")
      (node (ref "P1") (pin "B10") (pinfunction "B10_B10") (pintype "passive"))
    )
    (net (code "137") (name "/PCI_NC3") (class "Default")
      (node (ref "P1") (pin "A10") (pinfunction "A10_A10") (pintype "passive"))
    )
    (net (code "138") (name "/PCI_NC4") (class "Default")
      (node (ref "P1") (pin "A11") (pinfunction "A11_A11") (pintype "passive"))
    )
    (net (code "139") (name "/PCI_NC5") (class "Default")
      (node (ref "P1") (pin "B14") (pinfunction "B14_B14") (pintype "passive"))
    )
    (net (code "140") (name "/PCI_NC6") (class "Default")
      (node (ref "P1") (pin "A16") (pinfunction "A16_A16") (pintype "passive"))
    )
    (net (code "141") (name "/PCI_NC7") (class "Default")
      (node (ref "P1") (pin "B19") (pinfunction "B19_B19") (pintype "passive"))
    )
    (net (code "142") (name "/PCI_NC8") (class "Default")
      (node (ref "P1") (pin "B59") (pinfunction "B59_B59") (pintype "passive"))
    )
    (net (code "143") (name "/PCI_NC9") (class "Default")
      (node (ref "P1") (pin "A59") (pinfunction "A59_A59") (pintype "passive"))
    )
    (net (code "144") (name "/PERR#") (class "Default")
      (node (ref "P1") (pin "B40") (pinfunction "B40_B40") (pintype "passive"))
      (node (ref "U9") (pin "11") (pinfunction "A9_11") (pintype "passive"))
    )
    (net (code "145") (name "/PME#") (class "Default")
      (node (ref "P1") (pin "A19") (pinfunction "A19_A19") (pintype "passive"))
    )
    (net (code "146") (name "/PRSNT2#") (class "Default")
      (node (ref "P1") (pin "B11") (pinfunction "B11_B11") (pintype "passive"))
      (node (ref "R59") (pin "1") (pinfunction "1_1") (pintype "passive"))
    )
    (net (code "147") (name "/REQ#") (class "Default")
      (node (ref "P1") (pin "B18") (pinfunction "B18_B18") (pintype "passive"))
      (node (ref "U5") (pin "6") (pinfunction "A4_6") (pintype "passive"))
    )
    (net (code "148") (name "/REQ64#") (class "Default")
      (node (ref "P1") (pin "A60") (pinfunction "A60_A60") (pintype "passive"))
    )
    (net (code "149") (name "/RST#") (class "Default")
      (node (ref "P1") (pin "A15") (pinfunction "A15_A15") (pintype "passive"))
      (node (ref "U5") (pin "4") (pinfunction "A2_4") (pintype "passive"))
    )
    (net (code "150") (name "/SDRAM_A6") (class "Default")
      (node (ref "U8") (pin "152") (pinfunction "IO,_PLL2_OUTn_152") (pintype "bidirectional"))
    )
    (net (code "151") (name "/SDRAM_A7") (class "Default")
      (node (ref "U8") (pin "151") (pinfunction "IO,_PLL2_OUTp_151") (pintype "bidirectional"))
    )
    (net (code "152") (name "/SDRAM_A8") (class "Default")
      (node (ref "U8") (pin "150") (pinfunction "IO,_LVDS29p_150") (pintype "bidirectional"))
    )
    (net (code "153") (name "/SDRAM_A9") (class "Default")
      (node (ref "U8") (pin "149") (pinfunction "IO,_LVDS29n_149") (pintype "bidirectional"))
    )
    (net (code "154") (name "/SDRAM_A11") (class "Default")
      (node (ref "U8") (pin "147") (pinfunction "IO,_LVDS30p,_DQ0R0/DQ1R0_147") (pintype "bidirectional"))
    )
    (net (code "155") (name "/SDRAM_A12") (class "Default")
      (node (ref "U8") (pin "146") (pinfunction "IO,_LVDS30n,_DQ0R1/DQ1R1_146") (pintype "bidirectional"))
    )
    (net (code "156") (name "/SDRAM_CKE") (class "Default")
      (node (ref "U8") (pin "145") (pinfunction "IO,_VREFB3N0_145") (pintype "bidirectional"))
    )
    (net (code "157") (name "/SDRAM_CLK") (class "Default")
      (node (ref "U8") (pin "144") (pinfunction "IO,_LVDS31p,_DQ0R2/DQ1R2_144") (pintype "bidirectional"))
    )
    (net (code "158") (name "/SERR#") (class "Default")
      (node (ref "P1") (pin "B42") (pinfunction "B42_B42") (pintype "passive"))
      (node (ref "U11") (pin "2") (pinfunction "A0_2") (pintype "passive"))
    )
    (net (code "159") (name "/SMBCLK") (class "Default")
      (node (ref "P1") (pin "A40") (pinfunction "A40_A40") (pintype "passive"))
    )
    (net (code "160") (name "/SMBDAT") (class "Default")
      (node (ref "P1") (pin "A41") (pinfunction "A41_A41") (pintype "passive"))
    )
    (net (code "161") (name "/STOP#") (class "Default")
      (node (ref "P1") (pin "A38") (pinfunction "A38_A38") (pintype "passive"))
      (node (ref "U9") (pin "10") (pinfunction "A8_10") (pintype "passive"))
    )
    (net (code "162") (name "/SW1") (class "Default")
      (node (ref "U8") (pin "127") (pinfunction "IO,_LVDS36n,_DQ1R1/DQ1R10_127") (pintype "bidirectional"))
    )
    (net (code "163") (name "/SW2") (class "Default")
      (node (ref "U8") (pin "128") (pinfunction "IO,_LVDS36p,_(DPCLK6/DQS1R)/(DPCLK6/DQS1R)_128") (pintype "bidirectional"))
    )
    (net (code "164") (name "/SW8") (class "Default")
      (node (ref "U8") (pin "133") (pinfunction "IO,_LVDS35n,_DQ1R0/DQ1R9_133") (pintype "bidirectional"))
    )
    (net (code "165") (name "/TCK") (class "Default")
      (node (ref "P1") (pin "B2") (pinfunction "B2_B2") (pintype "passive"))
    )
    (net (code "166") (name "/TDIO") (class "Default")
      (node (ref "P1") (pin "A4") (pinfunction "A4_A4") (pintype "passive"))
      (node (ref "P1") (pin "B4") (pinfunction "B4_B4") (pintype "passive"))
    )
    (net (code "167") (name "/TMS") (class "Default")
      (node (ref "P1") (pin "A3") (pinfunction "A3_A3") (pintype "passive"))
    )
    (net (code "168") (name "/TRDY#") (class "Default")
      (node (ref "P1") (pin "A36") (pinfunction "A36_A36") (pintype "passive"))
      (node (ref "U9") (pin "8") (pinfunction "A6_8") (pintype "passive"))
    )
    (net (code "169") (name "/TRST#") (class "Default")
      (node (ref "P1") (pin "A1") (pinfunction "A1_A1") (pintype "passive"))
    )
    (net (code "170") (name "/UART_RX") (class "Default")
      (node (ref "U8") (pin "119") (pinfunction "IO,_LVDS37n_119") (pintype "bidirectional"))
    )
    (net (code "171") (name "/UART_TX") (class "Default")
      (node (ref "U8") (pin "120") (pinfunction "IO,_LVDS37p_120") (pintype "bidirectional"))
    )
    (net (code "172") (name "/VCC4V3") (class "Default")
      (node (ref "C17") (pin "2") (pinfunction "2_2") (pintype "passive"))
      (node (ref "C19") (pin "2") (pinfunction "2_2") (pintype "passive"))
      (node (ref "C20") (pin "2") (pinfunction "2_2") (pintype "passive"))
      (node (ref "C26") (pin "2") (pinfunction "2_2") (pintype "passive"))
      (node (ref "C27") (pin "2") (pinfunction "2_2") (pintype "passive"))
      (node (ref "C77") (pin "2") (pinfunction "2_2") (pintype "passive"))
      (node (ref "D1") (pin "2") (pinfunction "K_2") (pintype "passive"))
      (node (ref "D2") (pin "2") (pinfunction "K_2") (pintype "passive"))
      (node (ref "R60") (pin "1") (pinfunction "1_1") (pintype "passive"))
      (node (ref "TP1") (pin "1") (pinfunction "1_1") (pintype "passive"))
      (node (ref "U11") (pin "24") (pinfunction "VCC_24") (pintype "passive"))
      (node (ref "U12") (pin "24") (pinfunction "VCC_24") (pintype "passive"))
      (node (ref "U5") (pin "24") (pinfunction "VCC_24") (pintype "passive"))
      (node (ref "U7") (pin "24") (pinfunction "VCC_24") (pintype "passive"))
      (node (ref "U9") (pin "24") (pinfunction "VCC_24") (pintype "passive"))
    )
    (net (code "173") (name "/VGA_B") (class "Default")
      (node (ref "U8") (pin "138") (pinfunction "IO,_LVDS33n,_DQ0R7/DQ1R7_138") (pintype "bidirectional"))
    )
    (net (code "174") (name "/VGA_B_2") (class "Default")
      (node (ref "U8") (pin "137") (pinfunction "IO,_LVDS34p,__/DQ1R8_137") (pintype "bidirectional"))
    )
    (net (code "175") (name "/VGA_G") (class "Default")
      (node (ref "U8") (pin "141") (pinfunction "IO,_LVDS32n,_DQ0R5/DQ1R5_141") (pintype "bidirectional"))
    )
    (net (code "176") (name "/VGA_G_2") (class "Default")
      (node (ref "U8") (pin "139") (pinfunction "IO,_LVDS33p,_DQ0R6/DQ1R6_139") (pintype "bidirectional"))
    )
    (net (code "177") (name "/VGA_HSYNC") (class "Default")
      (node (ref "U8") (pin "135") (pinfunction "IO,_LVDS34n,_DM0R/(DM1R0/BWS#1R0)_135") (pintype "bidirectional"))
    )
    (net (code "178") (name "/VGA_R") (class "Default")
      (node (ref "U8") (pin "143") (pinfunction "IO,_LVDS31n,_DQ0R3/DQ1R3_143") (pintype "bidirectional"))
    )
    (net (code "179") (name "/VGA_R_2") (class "Default")
      (node (ref "U8") (pin "142") (pinfunction "IO,_LVDS32p,_DQ0R4/DQ1R4_142") (pintype "bidirectional"))
    )
    (net (code "180") (name "/VGA_VSYNC") (class "Default")
      (node (ref "U8") (pin "134") (pinfunction "IO,_LVDS35p,_(DPCLK7/DQS0R)/(DPCLK7/DQS0R)_134") (pintype "bidirectional"))
    )
    (net (code "181") (name "5V") (class "Default")
      (node (ref "C75") (pin "1") (pinfunction "1_1") (pintype "passive"))
      (node (ref "C76") (pin "2") (pinfunction "2_2") (pintype "passive"))
      (node (ref "D1") (pin "1") (pinfunction "A_1") (pintype "passive"))
      (node (ref "D2") (pin "1") (pinfunction "A_1") (pintype "passive"))
      (node (ref "P1") (pin "A5") (pinfunction "A5_A5") (pintype "passive"))
      (node (ref "P1") (pin "A61") (pinfunction "A61_A61") (pintype "passive"))
      (node (ref "P1") (pin "A62") (pinfunction "A62_A62") (pintype "passive"))
      (node (ref "P1") (pin "A8") (pinfunction "A8_A8") (pintype "passive"))
      (node (ref "P1") (pin "B5") (pinfunction "B5_B5") (pintype "passive"))
      (node (ref "P1") (pin "B6") (pinfunction "B6_B6") (pintype "passive"))
      (node (ref "P1") (pin "B61") (pinfunction "B61_B61") (pintype "passive"))
      (node (ref "P1") (pin "B62") (pinfunction "B62_B62") (pintype "passive"))
    )
    (net (code "182") (name "GND") (class "Default")
      (node (ref "C17") (pin "1") (pinfunction "1_1") (pintype "passive"))
      (node (ref "C19") (pin "1") (pinfunction "1_1") (pintype "passive"))
      (node (ref "C20") (pin "1") (pinfunction "1_1") (pintype "passive"))
      (node (ref "C26") (pin "1") (pinfunction "1_1") (pintype "passive"))
      (node (ref "C27") (pin "1") (pinfunction "1_1") (pintype "passive"))
      (node (ref "C75") (pin "2") (pinfunction "2_2") (pintype "passive"))
      (node (ref "C76") (pin "1") (pinfunction "1_1") (pintype "passive"))
      (node (ref "C77") (pin "1") (pinfunction "1_1") (pintype "passive"))
      (node (ref "P1") (pin "A18") (pinfunction "A18_A18") (pintype "passive"))
      (node (ref "P1") (pin "A24") (pinfunction "A24_A24") (pintype "passive"))
      (node (ref "P1") (pin "A30") (pinfunction "A30_A30") (pintype "passive"))
      (node (ref "P1") (pin "A35") (pinfunction "A35_A35") (pintype "passive"))
      (node (ref "P1") (pin "A37") (pinfunction "A37_A37") (pintype "passive"))
      (node (ref "P1") (pin "A42") (pinfunction "A42_A42") (pintype "passive"))
      (node (ref "P1") (pin "A48") (pinfunction "A48_A48") (pintype "passive"))
      (node (ref "P1") (pin "A56") (pinfunction "A56_A56") (pintype "passive"))
      (node (ref "P1") (pin "B15") (pinfunction "B15_B15") (pintype "passive"))
      (node (ref "P1") (pin "B17") (pinfunction "B17_B17") (pintype "passive"))
      (node (ref "P1") (pin "B22") (pinfunction "B22_B22") (pintype "passive"))
      (node (ref "P1") (pin "B28") (pinfunction "B28_B28") (pintype "passive"))
      (node (ref "P1") (pin "B3") (pinfunction "B3_B3") (pintype "passive"))
      (node (ref "P1") (pin "B34") (pinfunction "B34_B34") (pintype "passive"))
      (node (ref "P1") (pin "B38") (pinfunction "B38_B38") (pintype "passive"))
      (node (ref "P1") (pin "B46") (pinfunction "B46_B46") (pintype "passive"))
      (node (ref "P1") (pin "B57") (pinfunction "B57_B57") (pintype "passive"))
      (node (ref "P1") (pin "B9") (pinfunction "B9_B9") (pintype "passive"))
      (node (ref "R26") (pin "2") (pinfunction "2_2") (pintype "passive"))
      (node (ref "R59") (pin "2") (pinfunction "2_2") (pintype "passive"))
      (node (ref "R60") (pin "2") (pinfunction "2_2") (pintype "passive"))
      (node (ref "U11") (pin "12") (pinfunction "GND_12") (pintype "passive"))
      (node (ref "U11") (pin "23") (pinfunction "BE#_23") (pintype "passive"))
      (node (ref "U12") (pin "12") (pinfunction "GND_12") (pintype "passive"))
      (node (ref "U12") (pin "23") (pinfunction "BE#_23") (pintype "passive"))
      (node (ref "U5") (pin "12") (pinfunction "GND_12") (pintype "passive"))
      (node (ref "U5") (pin "23") (pinfunction "BE#_23") (pintype "passive"))
      (node (ref "U7") (pin "12") (pinfunction "GND_12") (pintype "passive"))
      (node (ref "U7") (pin "23") (pinfunction "BE#_23") (pintype "passive"))
      (node (ref "U9") (pin "12") (pinfunction "GND_12") (pintype "passive"))
      (node (ref "U9") (pin "23") (pinfunction "BE#_23") (pintype "passive"))
    )
    (net (code "183") (name "unconnected-(U5-NC-Pad1)") (class "Default")
      (node (ref "U5") (pin "1") (pinfunction "NC_1") (pintype "passive"))
    )
    (net (code "184") (name "unconnected-(U7-NC-Pad1)") (class "Default")
      (node (ref "U7") (pin "1") (pinfunction "NC_1") (pintype "passive"))
    )
    (net (code "185") (name "unconnected-(U9-NC-Pad1)") (class "Default")
      (node (ref "U9") (pin "1") (pinfunction "NC_1") (pintype "passive"))
    )
    (net (code "186") (name "unconnected-(U11-NC-Pad1)") (class "Default")
      (node (ref "U11") (pin "1") (pinfunction "NC_1") (pintype "passive"))
    )
    (net (code "187") (name "unconnected-(U12-NC-Pad1)") (class "Default")
      (node (ref "U12") (pin "1") (pinfunction "NC_1") (pintype "passive"))
    )
  )
)
